# MechModule.net
KiCad netlist of a schematic drawn in EAGLE
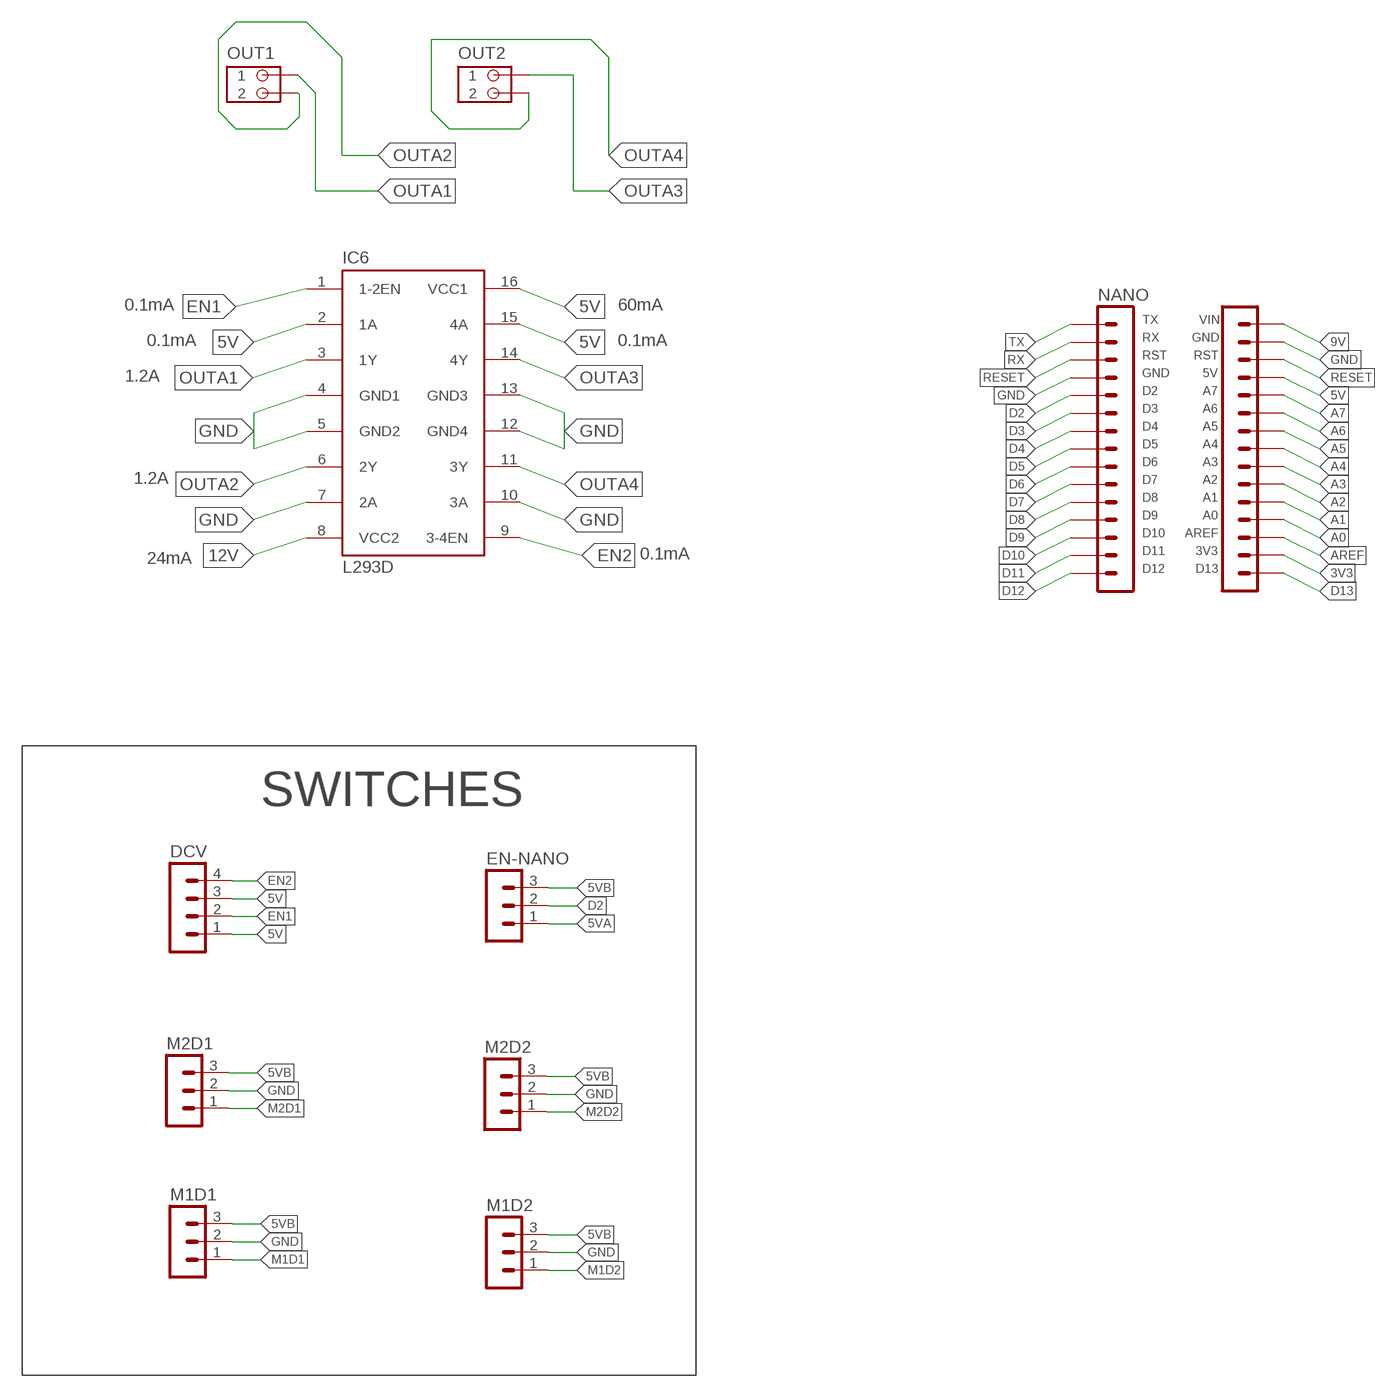
[diagram p0: schematic, sheet 1, part 1 of 3]
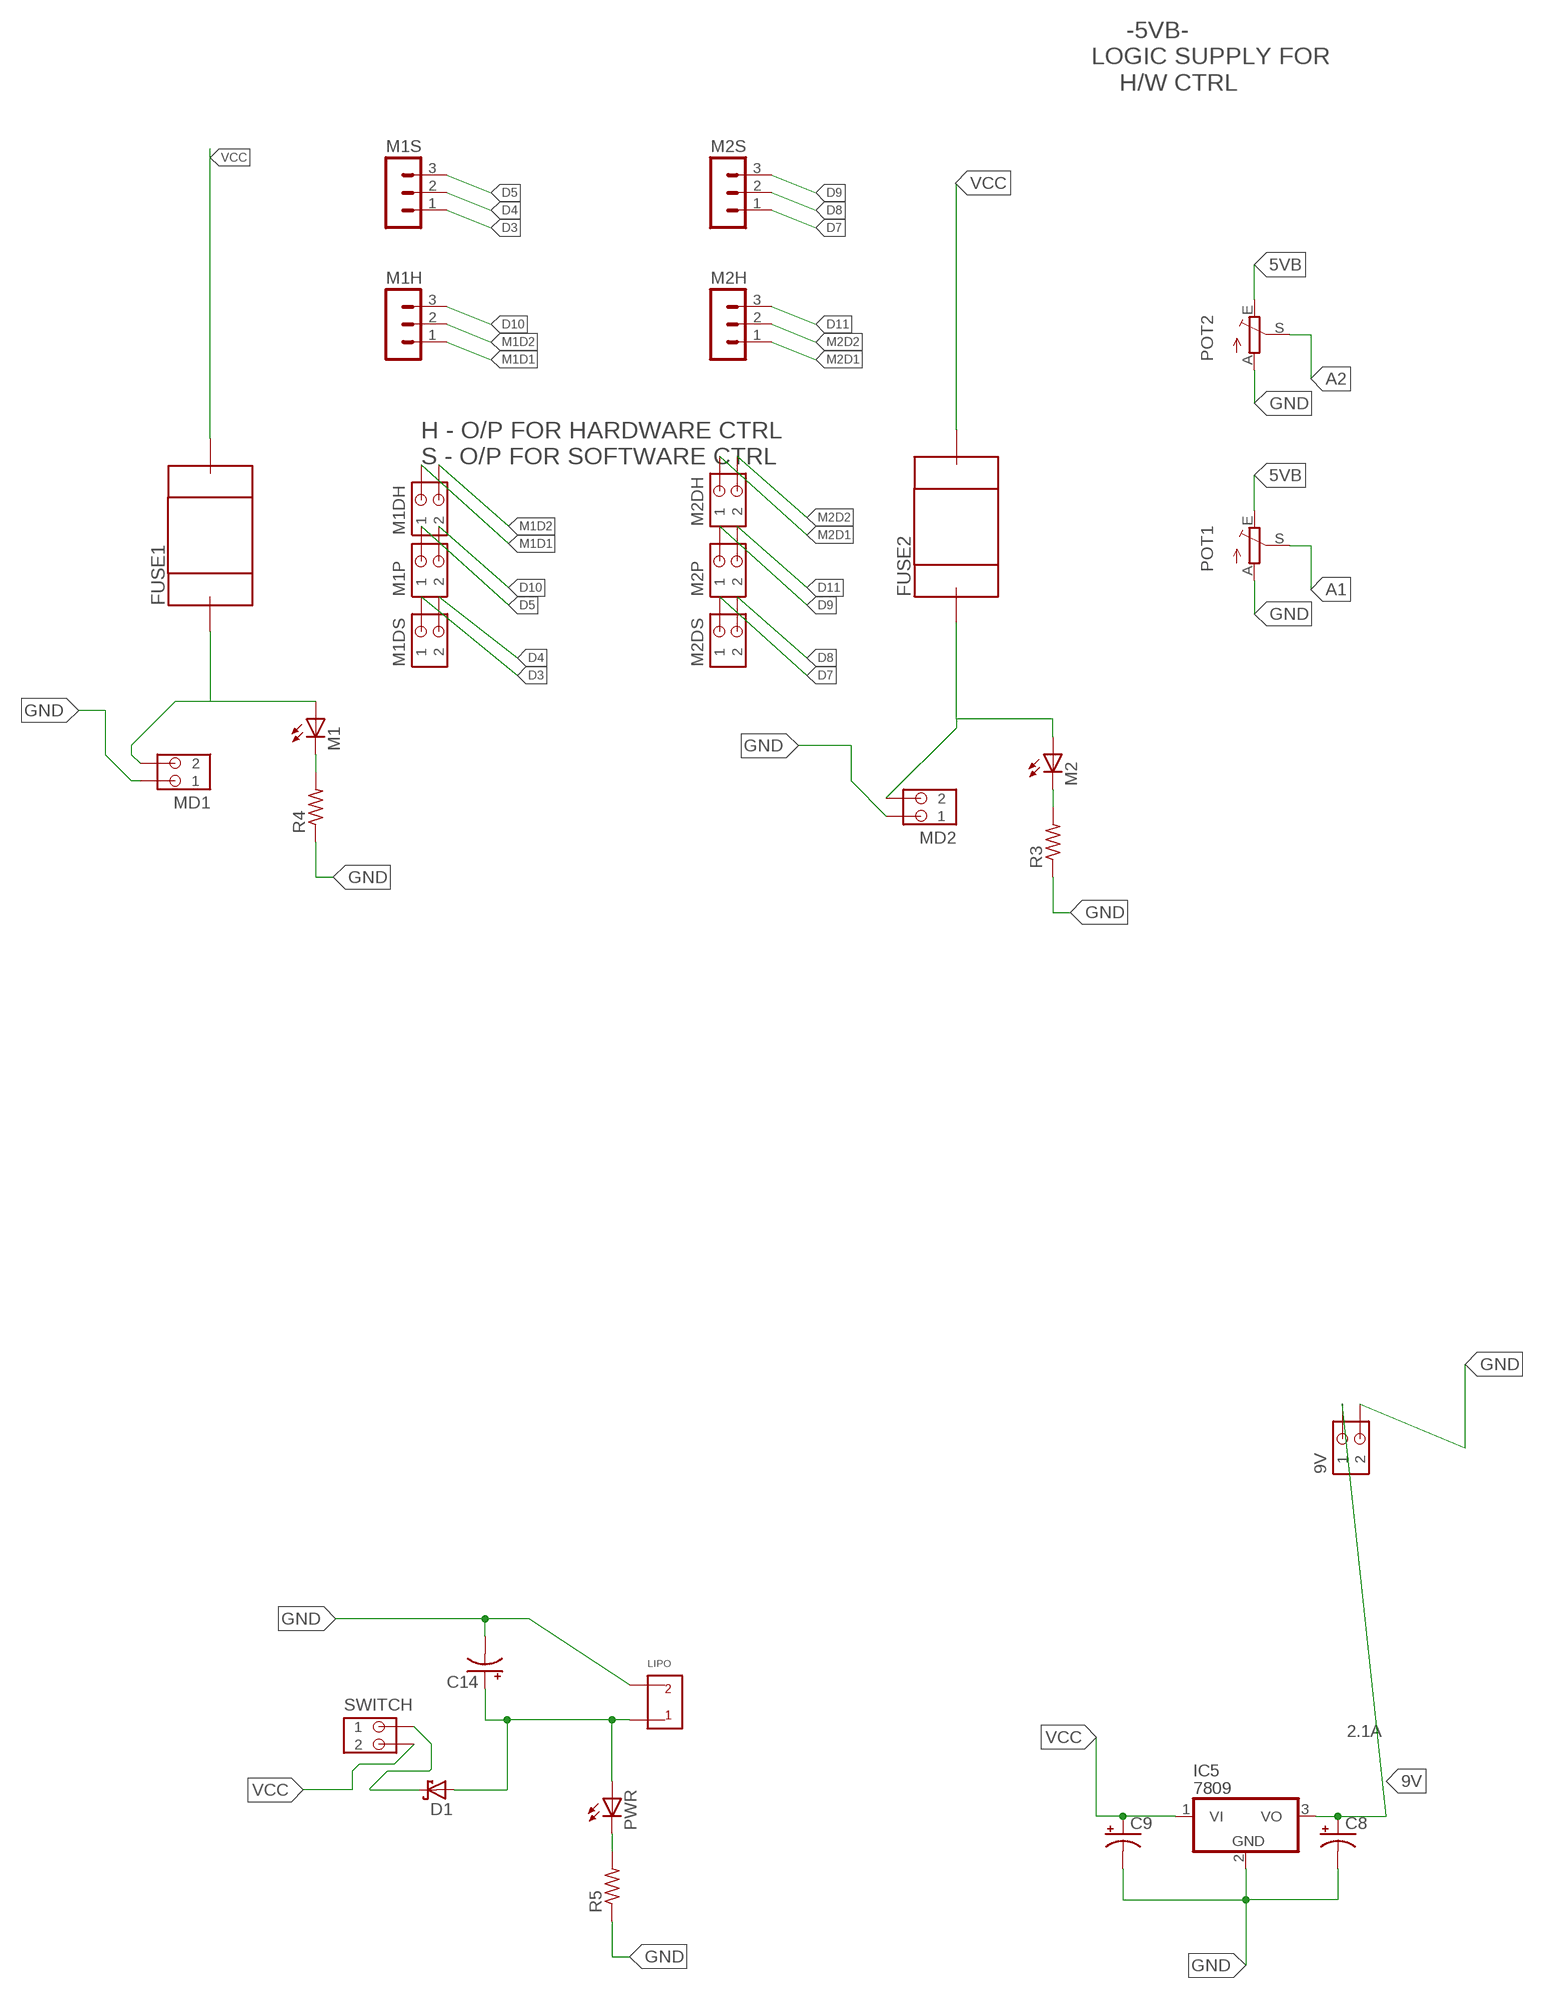
[diagram p1: schematic, sheet 1, part 2 of 3]
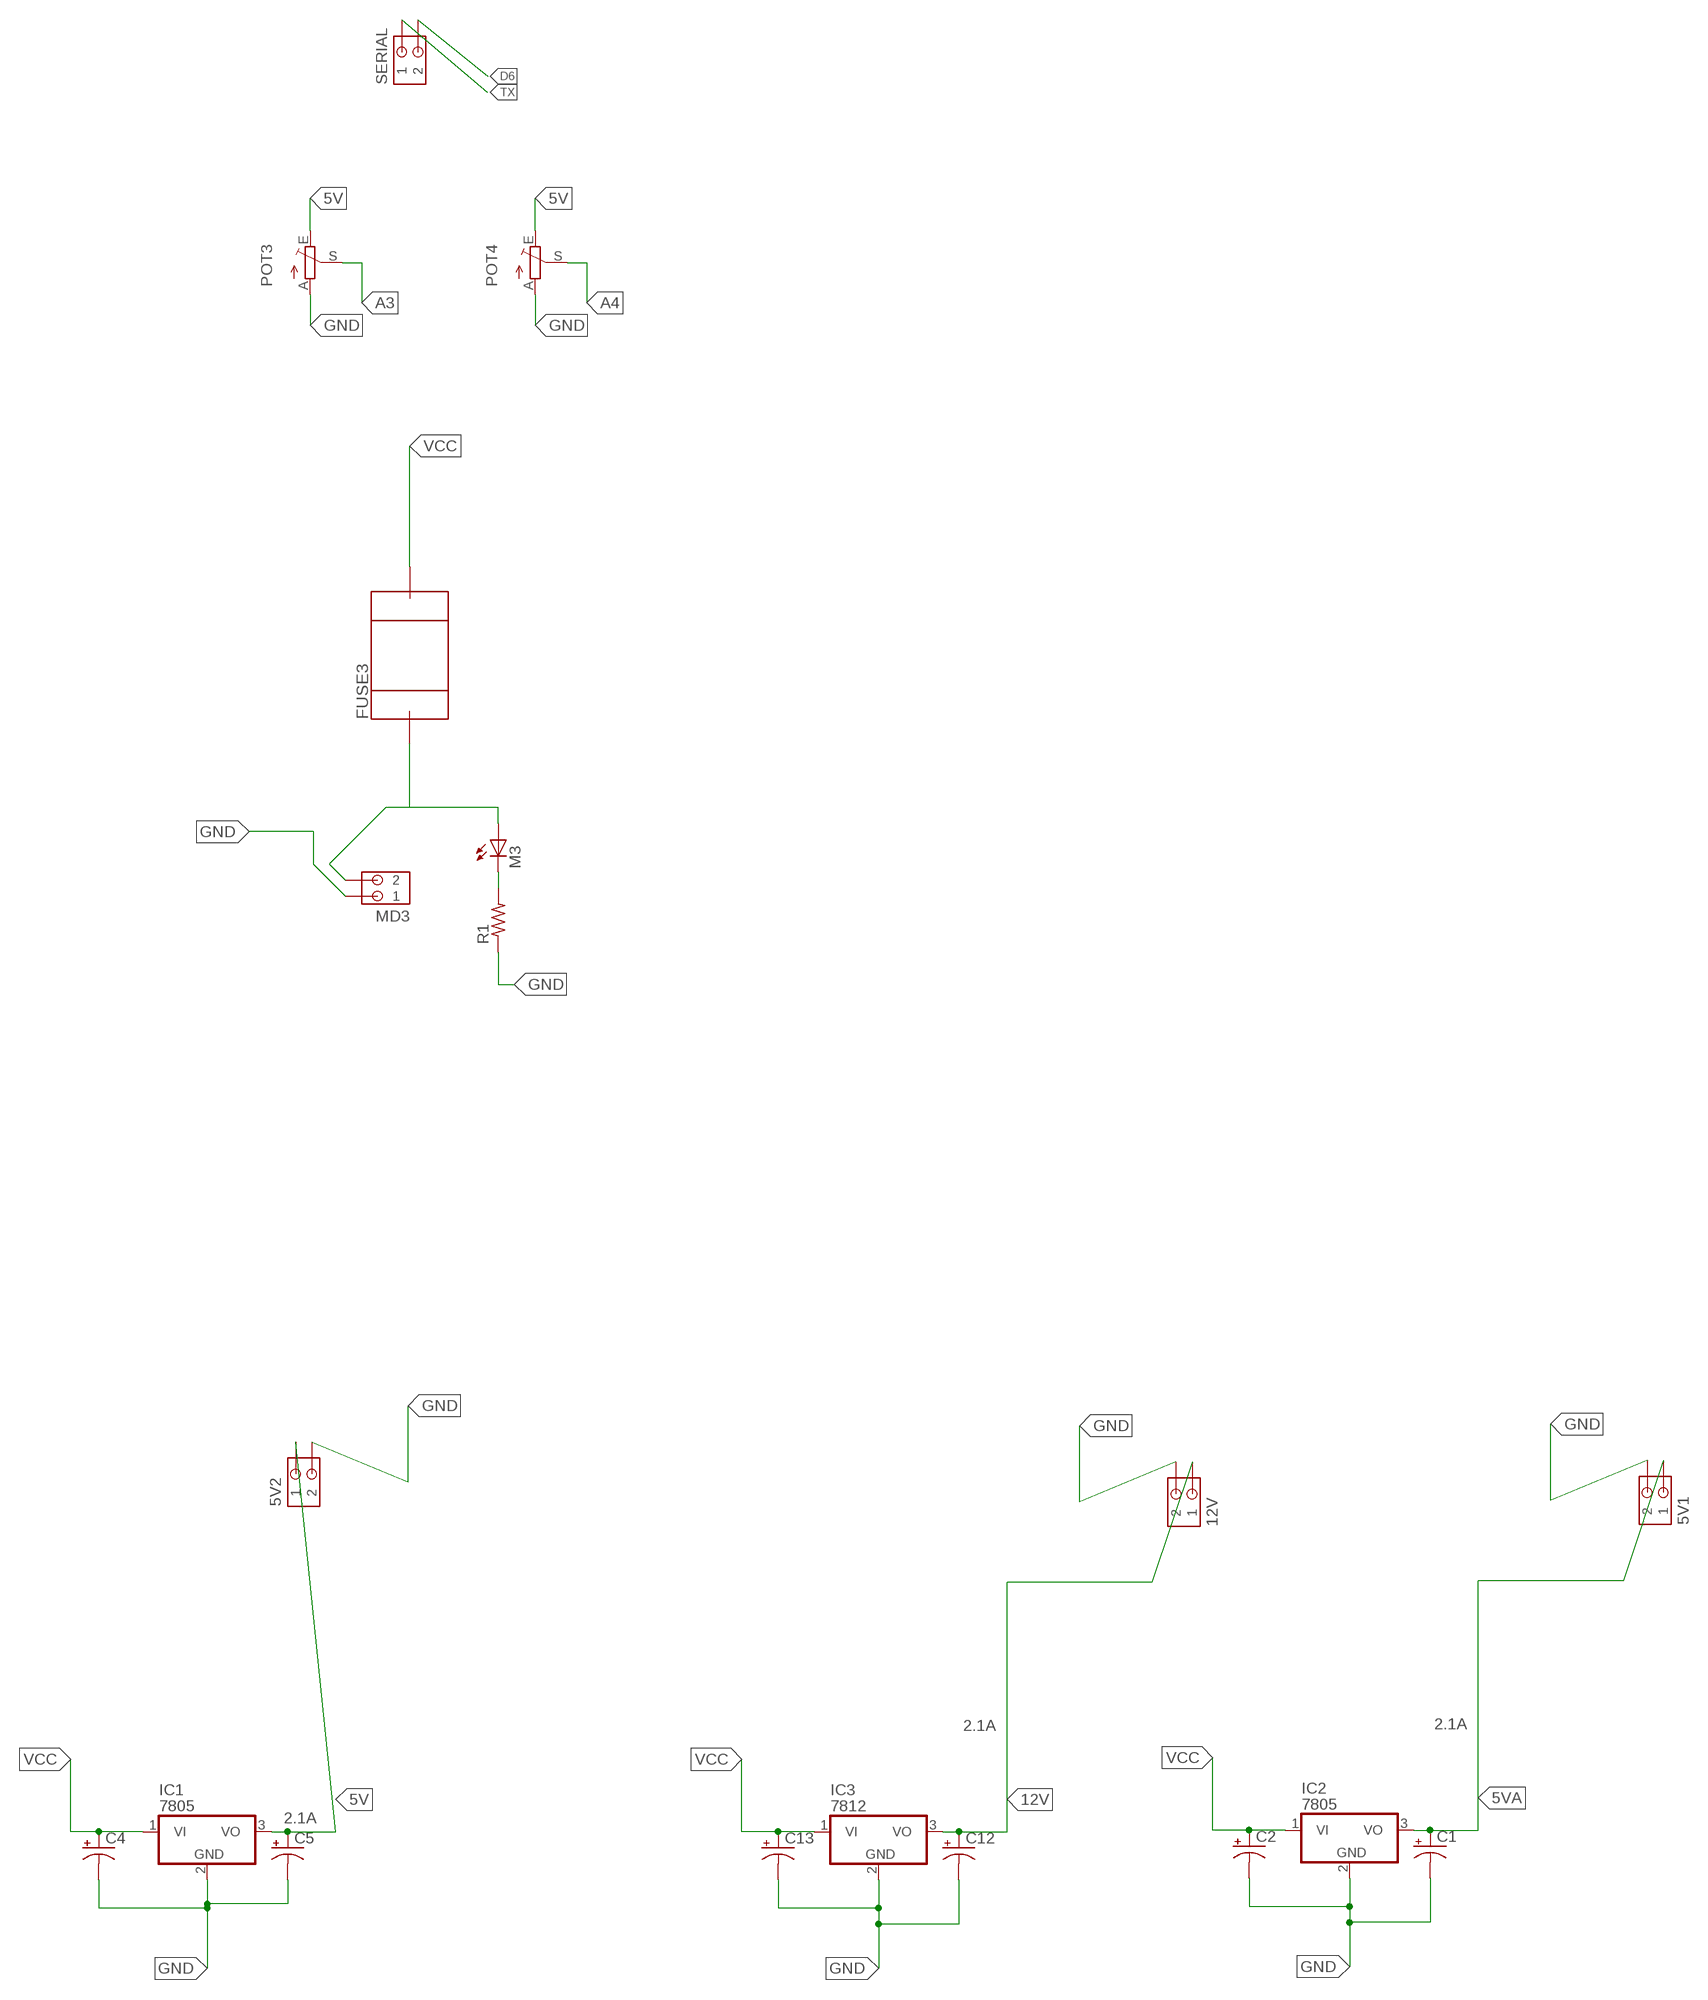
[diagram p2: schematic, sheet 1, part 3 of 3]

(export (version "E")
  (design (tool "Eeschema 10.0.6"))
  (components
    (comp (ref "5V1")
      (value "SCREWCONN")
      (footprint "eagle-import:STANDARD")
      (libsource (lib "eagle-import") (part "SCREWCONN"))
    )
    (comp (ref "5V2")
      (value "SCREWCONN")
      (footprint "eagle-import:STANDARD")
      (libsource (lib "eagle-import") (part "SCREWCONN"))
    )
    (comp (ref "9V")
      (value "SCREWCONN")
      (footprint "eagle-import:STANDARD")
      (libsource (lib "eagle-import") (part "SCREWCONN"))
    )
    (comp (ref "12V")
      (value "SCREWCONN")
      (footprint "eagle-import:STANDARD")
      (libsource (lib "eagle-import") (part "SCREWCONN"))
    )
    (comp (ref "C1")
      (value "CPOL-USE2-5")
      (footprint "eagle-import:E2-5")
      (libsource (lib "eagle-import") (part "CPOL-USE2-5"))
    )
    (comp (ref "C2")
      (value "CPOL-USE2-5")
      (footprint "eagle-import:E2-5")
      (libsource (lib "eagle-import") (part "CPOL-USE2-5"))
    )
    (comp (ref "C4")
      (value "CPOL-USE2-5")
      (footprint "eagle-import:E2-5")
      (libsource (lib "eagle-import") (part "CPOL-USE2-5"))
    )
    (comp (ref "C5")
      (value "CPOL-USE2-5")
      (footprint "eagle-import:E2-5")
      (libsource (lib "eagle-import") (part "CPOL-USE2-5"))
    )
    (comp (ref "C8")
      (value "CPOL-USE2-5")
      (footprint "eagle-import:E2-5")
      (libsource (lib "eagle-import") (part "CPOL-USE2-5"))
    )
    (comp (ref "C9")
      (value "CPOL-USE2-5")
      (footprint "eagle-import:E2-5")
      (libsource (lib "eagle-import") (part "CPOL-USE2-5"))
    )
    (comp (ref "C12")
      (value "CPOL-USE2-5")
      (footprint "eagle-import:E2-5")
      (libsource (lib "eagle-import") (part "CPOL-USE2-5"))
    )
    (comp (ref "C13")
      (value "CPOL-USE2-5")
      (footprint "eagle-import:E2-5")
      (libsource (lib "eagle-import") (part "CPOL-USE2-5"))
    )
    (comp (ref "C14")
      (value "CPOL-USE7.5-16")
      (footprint "eagle-import:E7,5-16")
      (libsource (lib "eagle-import") (part "CPOL-USE7.5-16"))
    )
    (comp (ref "D1")
      (value "5KPXX")
      (footprint "eagle-import:P6T15")
      (libsource (lib "eagle-import") (part "5KPXX"))
    )
    (comp (ref "DCV")
      (value "MA04-1")
      (footprint "eagle-import:MA04-1")
      (libsource (lib "eagle-import") (part "MA04-1"))
    )
    (comp (ref "EN-NANO")
      (value "MA03-1")
      (footprint "eagle-import:MA03-1")
      (libsource (lib "eagle-import") (part "MA03-1"))
    )
    (comp (ref "FUSE1")
      (value "CPT-FUSE")
      (footprint "eagle-import:CPT-FUSES")
      (libsource (lib "eagle-import") (part "CPT-FUSE"))
    )
    (comp (ref "FUSE2")
      (value "CPT-FUSE")
      (footprint "eagle-import:CPT-FUSES")
      (libsource (lib "eagle-import") (part "CPT-FUSE"))
    )
    (comp (ref "FUSE3")
      (value "CPT-FUSE")
      (footprint "eagle-import:CPT-FUSES")
      (libsource (lib "eagle-import") (part "CPT-FUSE"))
    )
    (comp (ref "IC1")
      (value "7805")
      (footprint "eagle-import:78XX")
      (libsource (lib "eagle-import") (part "7805"))
    )
    (comp (ref "IC2")
      (value "7805")
      (footprint "eagle-import:78XX")
      (libsource (lib "eagle-import") (part "7805"))
    )
    (comp (ref "IC3")
      (value "7812")
      (footprint "eagle-import:78XX")
      (libsource (lib "eagle-import") (part "7812"))
    )
    (comp (ref "IC5")
      (value "7809")
      (footprint "eagle-import:78XX")
      (libsource (lib "eagle-import") (part "7809"))
    )
    (comp (ref "IC6")
      (value "L293D")
      (footprint "eagle-import:DIL16")
      (libsource (lib "eagle-import") (part "L293D"))
    )
    (comp (ref "LIPO")
      (value "SCREW_XT-60")
      (footprint "eagle-import:SCREW_XT-60")
      (libsource (lib "eagle-import") (part "SCREW_XT-60"))
    )
    (comp (ref "M1")
      (value "LED5MM")
      (footprint "eagle-import:LED5MM")
      (libsource (lib "eagle-import") (part "LED5MM"))
    )
    (comp (ref "M1D1")
      (value "MA03-1")
      (footprint "eagle-import:MA03-1")
      (libsource (lib "eagle-import") (part "MA03-1"))
    )
    (comp (ref "M1D2")
      (value "MA03-1")
      (footprint "eagle-import:MA03-1")
      (libsource (lib "eagle-import") (part "MA03-1"))
    )
    (comp (ref "M1DH")
      (value "SCREWCONN")
      (footprint "eagle-import:STANDARD")
      (libsource (lib "eagle-import") (part "SCREWCONN"))
    )
    (comp (ref "M1DS")
      (value "SCREWCONN")
      (footprint "eagle-import:STANDARD")
      (libsource (lib "eagle-import") (part "SCREWCONN"))
    )
    (comp (ref "M1H")
      (value "MA03-1")
      (footprint "eagle-import:MA03-1")
      (libsource (lib "eagle-import") (part "MA03-1"))
    )
    (comp (ref "M1P")
      (value "SCREWCONN")
      (footprint "eagle-import:STANDARD")
      (libsource (lib "eagle-import") (part "SCREWCONN"))
    )
    (comp (ref "M1S")
      (value "MA03-1")
      (footprint "eagle-import:MA03-1")
      (libsource (lib "eagle-import") (part "MA03-1"))
    )
    (comp (ref "M2")
      (value "LED5MM")
      (footprint "eagle-import:LED5MM")
      (libsource (lib "eagle-import") (part "LED5MM"))
    )
    (comp (ref "M2D1")
      (value "MA03-1")
      (footprint "eagle-import:MA03-1")
      (libsource (lib "eagle-import") (part "MA03-1"))
    )
    (comp (ref "M2D2")
      (value "MA03-1")
      (footprint "eagle-import:MA03-1")
      (libsource (lib "eagle-import") (part "MA03-1"))
    )
    (comp (ref "M2DH")
      (value "SCREWCONN")
      (footprint "eagle-import:STANDARD")
      (libsource (lib "eagle-import") (part "SCREWCONN"))
    )
    (comp (ref "M2DS")
      (value "SCREWCONN")
      (footprint "eagle-import:STANDARD")
      (libsource (lib "eagle-import") (part "SCREWCONN"))
    )
    (comp (ref "M2H")
      (value "MA03-1")
      (footprint "eagle-import:MA03-1")
      (libsource (lib "eagle-import") (part "MA03-1"))
    )
    (comp (ref "M2P")
      (value "SCREWCONN")
      (footprint "eagle-import:STANDARD")
      (libsource (lib "eagle-import") (part "SCREWCONN"))
    )
    (comp (ref "M2S")
      (value "MA03-1")
      (footprint "eagle-import:MA03-1")
      (libsource (lib "eagle-import") (part "MA03-1"))
    )
    (comp (ref "M3")
      (value "LED5MM")
      (footprint "eagle-import:LED5MM")
      (libsource (lib "eagle-import") (part "LED5MM"))
    )
    (comp (ref "MD1")
      (value "SCREWCONN")
      (footprint "eagle-import:STANDARD")
      (libsource (lib "eagle-import") (part "SCREWCONN"))
    )
    (comp (ref "MD2")
      (value "SCREWCONN")
      (footprint "eagle-import:STANDARD")
      (libsource (lib "eagle-import") (part "SCREWCONN"))
    )
    (comp (ref "MD3")
      (value "SCREWCONN")
      (footprint "eagle-import:STANDARD")
      (libsource (lib "eagle-import") (part "SCREWCONN"))
    )
    (comp (ref "NANO")
      (value "ARD-NANO")
      (footprint "eagle-import:ARD-NANO")
      (libsource (lib "eagle-import") (part "ARD-NANO"))
    )
    (comp (ref "OUT1")
      (value "SCREWCONN")
      (footprint "eagle-import:STANDARD")
      (libsource (lib "eagle-import") (part "SCREWCONN"))
    )
    (comp (ref "OUT2")
      (value "SCREWCONN")
      (footprint "eagle-import:STANDARD")
      (libsource (lib "eagle-import") (part "SCREWCONN"))
    )
    (comp (ref "POT1")
      (value "TRIM_EU-CA6V")
      (footprint "eagle-import:CA6V")
      (libsource (lib "eagle-import") (part "TRIM_EU-CA6V"))
    )
    (comp (ref "POT2")
      (value "TRIM_EU-CA6V")
      (footprint "eagle-import:CA6V")
      (libsource (lib "eagle-import") (part "TRIM_EU-CA6V"))
    )
    (comp (ref "POT3")
      (value "TRIM_EU-CA6V")
      (footprint "eagle-import:CA6V")
      (libsource (lib "eagle-import") (part "TRIM_EU-CA6V"))
    )
    (comp (ref "POT4")
      (value "TRIM_EU-CA6V")
      (footprint "eagle-import:CA6V")
      (libsource (lib "eagle-import") (part "TRIM_EU-CA6V"))
    )
    (comp (ref "PWR")
      (value "LED5MM")
      (footprint "eagle-import:LED5MM")
      (libsource (lib "eagle-import") (part "LED5MM"))
    )
    (comp (ref "R1")
      (value "R-US_0204/7")
      (footprint "eagle-import:0204_7")
      (libsource (lib "eagle-import") (part "R-US_0204/7"))
    )
    (comp (ref "R3")
      (value "R-US_0204/7")
      (footprint "eagle-import:0204_7")
      (libsource (lib "eagle-import") (part "R-US_0204/7"))
    )
    (comp (ref "R4")
      (value "R-US_0204/7")
      (footprint "eagle-import:0204_7")
      (libsource (lib "eagle-import") (part "R-US_0204/7"))
    )
    (comp (ref "R5")
      (value "R-US_0204/7")
      (footprint "eagle-import:0204_7")
      (libsource (lib "eagle-import") (part "R-US_0204/7"))
    )
    (comp (ref "SERIAL")
      (value "SCREWCONN")
      (footprint "eagle-import:STANDARD")
      (libsource (lib "eagle-import") (part "SCREWCONN"))
    )
    (comp (ref "SWITCH")
      (value "SCREWCONN")
      (footprint "eagle-import:STANDARD")
      (libsource (lib "eagle-import") (part "SCREWCONN"))
    )
  )
  (nets
    (net (code "1") (name "3V3") (class "Default")
      (node (ref "NANO") (pin "3V3") (pinfunction "3V3_3V3") (pintype "passive"))
    )
    (net (code "2") (name "5V") (class "Default")
      (node (ref "5V2") (pin "3") (pinfunction "1_3") (pintype "bidirectional"))
      (node (ref "C5") (pin "+") (pinfunction "+_+") (pintype "passive"))
      (node (ref "DCV") (pin "1") (pinfunction "1_1") (pintype "passive"))
      (node (ref "DCV") (pin "3") (pinfunction "3_3") (pintype "passive"))
      (node (ref "IC1") (pin "3") (pinfunction "VO_3") (pintype "passive"))
      (node (ref "IC6") (pin "15") (pinfunction "4A_15") (pintype "input"))
      (node (ref "IC6") (pin "16") (pinfunction "VCC1_16") (pintype "power_in"))
      (node (ref "IC6") (pin "2") (pinfunction "1A_2") (pintype "input"))
      (node (ref "NANO") (pin "5V") (pinfunction "5V_5V") (pintype "passive"))
      (node (ref "POT3") (pin "E") (pinfunction "E_E") (pintype "passive"))
      (node (ref "POT4") (pin "E") (pinfunction "E_E") (pintype "passive"))
    )
    (net (code "3") (name "5VA") (class "Default")
      (node (ref "5V1") (pin "3") (pinfunction "1_3") (pintype "bidirectional"))
      (node (ref "C1") (pin "+") (pinfunction "+_+") (pintype "passive"))
      (node (ref "EN-NANO") (pin "1") (pinfunction "1_1") (pintype "passive"))
      (node (ref "IC2") (pin "3") (pinfunction "VO_3") (pintype "passive"))
    )
    (net (code "4") (name "5VB") (class "Default")
      (node (ref "EN-NANO") (pin "3") (pinfunction "3_3") (pintype "passive"))
      (node (ref "M1D1") (pin "3") (pinfunction "3_3") (pintype "passive"))
      (node (ref "M1D2") (pin "3") (pinfunction "3_3") (pintype "passive"))
      (node (ref "M2D1") (pin "3") (pinfunction "3_3") (pintype "passive"))
      (node (ref "M2D2") (pin "3") (pinfunction "3_3") (pintype "passive"))
      (node (ref "POT1") (pin "E") (pinfunction "E_E") (pintype "passive"))
      (node (ref "POT2") (pin "E") (pinfunction "E_E") (pintype "passive"))
    )
    (net (code "5") (name "9V") (class "Default")
      (node (ref "9V") (pin "3") (pinfunction "1_3") (pintype "bidirectional"))
      (node (ref "C8") (pin "+") (pinfunction "+_+") (pintype "passive"))
      (node (ref "IC5") (pin "3") (pinfunction "VO_3") (pintype "passive"))
      (node (ref "NANO") (pin "VIN") (pinfunction "VIN_VIN") (pintype "passive"))
    )
    (net (code "6") (name "12V") (class "Default")
      (node (ref "12V") (pin "3") (pinfunction "1_3") (pintype "bidirectional"))
      (node (ref "C12") (pin "+") (pinfunction "+_+") (pintype "passive"))
      (node (ref "IC3") (pin "3") (pinfunction "VO_3") (pintype "passive"))
      (node (ref "IC6") (pin "8") (pinfunction "VCC2_8") (pintype "power_in"))
    )
    (net (code "7") (name "A0") (class "Default")
      (node (ref "NANO") (pin "A0") (pinfunction "A0_A0") (pintype "passive"))
    )
    (net (code "8") (name "A1") (class "Default")
      (node (ref "NANO") (pin "A1") (pinfunction "A1_A1") (pintype "passive"))
      (node (ref "POT1") (pin "S") (pinfunction "S_S") (pintype "passive"))
    )
    (net (code "9") (name "A2") (class "Default")
      (node (ref "NANO") (pin "A2") (pinfunction "A2_A2") (pintype "passive"))
      (node (ref "POT2") (pin "S") (pinfunction "S_S") (pintype "passive"))
    )
    (net (code "10") (name "A3") (class "Default")
      (node (ref "NANO") (pin "A3") (pinfunction "A3_A3") (pintype "passive"))
      (node (ref "POT3") (pin "S") (pinfunction "S_S") (pintype "passive"))
    )
    (net (code "11") (name "A4") (class "Default")
      (node (ref "NANO") (pin "A4") (pinfunction "A4_A4") (pintype "passive"))
      (node (ref "POT4") (pin "S") (pinfunction "S_S") (pintype "passive"))
    )
    (net (code "12") (name "A5") (class "Default")
      (node (ref "NANO") (pin "A5") (pinfunction "A5_A5") (pintype "passive"))
    )
    (net (code "13") (name "A6") (class "Default")
      (node (ref "NANO") (pin "A6") (pinfunction "A6_A6") (pintype "passive"))
    )
    (net (code "14") (name "A7") (class "Default")
      (node (ref "NANO") (pin "A7") (pinfunction "A7_A7") (pintype "passive"))
    )
    (net (code "15") (name "AREF") (class "Default")
      (node (ref "NANO") (pin "AREF") (pinfunction "AREF_AREF") (pintype "passive"))
    )
    (net (code "16") (name "D2") (class "Default")
      (node (ref "EN-NANO") (pin "2") (pinfunction "2_2") (pintype "passive"))
      (node (ref "NANO") (pin "D2") (pinfunction "D2_D2") (pintype "passive"))
    )
    (net (code "17") (name "D3") (class "Default")
      (node (ref "M1DS") (pin "3") (pinfunction "1_3") (pintype "bidirectional"))
      (node (ref "M1S") (pin "1") (pinfunction "1_1") (pintype "passive"))
      (node (ref "NANO") (pin "D3") (pinfunction "D3_D3") (pintype "passive"))
    )
    (net (code "18") (name "D4") (class "Default")
      (node (ref "M1DS") (pin "4") (pinfunction "2_4") (pintype "bidirectional"))
      (node (ref "M1S") (pin "2") (pinfunction "2_2") (pintype "passive"))
      (node (ref "NANO") (pin "D4") (pinfunction "D4_D4") (pintype "passive"))
    )
    (net (code "19") (name "D5") (class "Default")
      (node (ref "M1P") (pin "3") (pinfunction "1_3") (pintype "bidirectional"))
      (node (ref "M1S") (pin "3") (pinfunction "3_3") (pintype "passive"))
      (node (ref "NANO") (pin "D5") (pinfunction "D5_D5") (pintype "passive"))
    )
    (net (code "20") (name "D6") (class "Default")
      (node (ref "NANO") (pin "D6") (pinfunction "D6_D6") (pintype "passive"))
      (node (ref "SERIAL") (pin "4") (pinfunction "2_4") (pintype "bidirectional"))
    )
    (net (code "21") (name "D7") (class "Default")
      (node (ref "M2DS") (pin "3") (pinfunction "1_3") (pintype "bidirectional"))
      (node (ref "M2S") (pin "1") (pinfunction "1_1") (pintype "passive"))
      (node (ref "NANO") (pin "D7") (pinfunction "D7_D7") (pintype "passive"))
    )
    (net (code "22") (name "D8") (class "Default")
      (node (ref "M2DS") (pin "4") (pinfunction "2_4") (pintype "bidirectional"))
      (node (ref "M2S") (pin "2") (pinfunction "2_2") (pintype "passive"))
      (node (ref "NANO") (pin "D8") (pinfunction "D8_D8") (pintype "passive"))
    )
    (net (code "23") (name "D9") (class "Default")
      (node (ref "M2P") (pin "3") (pinfunction "1_3") (pintype "bidirectional"))
      (node (ref "M2S") (pin "3") (pinfunction "3_3") (pintype "passive"))
      (node (ref "NANO") (pin "D9") (pinfunction "D9_D9") (pintype "passive"))
    )
    (net (code "24") (name "D10") (class "Default")
      (node (ref "M1H") (pin "3") (pinfunction "3_3") (pintype "passive"))
      (node (ref "M1P") (pin "4") (pinfunction "2_4") (pintype "bidirectional"))
      (node (ref "NANO") (pin "D10") (pinfunction "D10_D10") (pintype "passive"))
    )
    (net (code "25") (name "D11") (class "Default")
      (node (ref "M2H") (pin "3") (pinfunction "3_3") (pintype "passive"))
      (node (ref "M2P") (pin "4") (pinfunction "2_4") (pintype "bidirectional"))
      (node (ref "NANO") (pin "D11") (pinfunction "D11_D11") (pintype "passive"))
    )
    (net (code "26") (name "D12") (class "Default")
      (node (ref "NANO") (pin "D12") (pinfunction "D12_D12") (pintype "passive"))
    )
    (net (code "27") (name "D13") (class "Default")
      (node (ref "NANO") (pin "D13") (pinfunction "D13_D13") (pintype "passive"))
    )
    (net (code "28") (name "EN1") (class "Default")
      (node (ref "DCV") (pin "2") (pinfunction "2_2") (pintype "passive"))
      (node (ref "IC6") (pin "1") (pinfunction "1-2EN_1") (pintype "input"))
    )
    (net (code "29") (name "EN2") (class "Default")
      (node (ref "DCV") (pin "4") (pinfunction "4_4") (pintype "passive"))
      (node (ref "IC6") (pin "9") (pinfunction "3-4EN_9") (pintype "input"))
    )
    (net (code "30") (name "GND") (class "Default")
      (node (ref "12V") (pin "4") (pinfunction "2_4") (pintype "bidirectional"))
      (node (ref "5V1") (pin "4") (pinfunction "2_4") (pintype "bidirectional"))
      (node (ref "5V2") (pin "4") (pinfunction "2_4") (pintype "bidirectional"))
      (node (ref "9V") (pin "4") (pinfunction "2_4") (pintype "bidirectional"))
      (node (ref "C1") (pin "-") (pinfunction "-_-") (pintype "passive"))
      (node (ref "C12") (pin "-") (pinfunction "-_-") (pintype "passive"))
      (node (ref "C13") (pin "-") (pinfunction "-_-") (pintype "passive"))
      (node (ref "C14") (pin "-") (pinfunction "-_-") (pintype "passive"))
      (node (ref "C2") (pin "-") (pinfunction "-_-") (pintype "passive"))
      (node (ref "C4") (pin "-") (pinfunction "-_-") (pintype "passive"))
      (node (ref "C5") (pin "-") (pinfunction "-_-") (pintype "passive"))
      (node (ref "C8") (pin "-") (pinfunction "-_-") (pintype "passive"))
      (node (ref "C9") (pin "-") (pinfunction "-_-") (pintype "passive"))
      (node (ref "IC1") (pin "2") (pinfunction "GND_2") (pintype "passive"))
      (node (ref "IC2") (pin "2") (pinfunction "GND_2") (pintype "passive"))
      (node (ref "IC3") (pin "2") (pinfunction "GND_2") (pintype "passive"))
      (node (ref "IC5") (pin "2") (pinfunction "GND_2") (pintype "passive"))
      (node (ref "IC6") (pin "10") (pinfunction "3A_10") (pintype "input"))
      (node (ref "IC6") (pin "12") (pinfunction "GND4_12") (pintype "power_in"))
      (node (ref "IC6") (pin "13") (pinfunction "GND3_13") (pintype "power_in"))
      (node (ref "IC6") (pin "4") (pinfunction "GND1_4") (pintype "power_in"))
      (node (ref "IC6") (pin "5") (pinfunction "GND2_5") (pintype "power_in"))
      (node (ref "IC6") (pin "7") (pinfunction "2A_7") (pintype "input"))
      (node (ref "LIPO") (pin "P$2") (pinfunction "P$2_P$2") (pintype "bidirectional"))
      (node (ref "M1D1") (pin "2") (pinfunction "2_2") (pintype "passive"))
      (node (ref "M1D2") (pin "2") (pinfunction "2_2") (pintype "passive"))
      (node (ref "M2D1") (pin "2") (pinfunction "2_2") (pintype "passive"))
      (node (ref "M2D2") (pin "2") (pinfunction "2_2") (pintype "passive"))
      (node (ref "MD1") (pin "3") (pinfunction "1_3") (pintype "bidirectional"))
      (node (ref "MD2") (pin "3") (pinfunction "1_3") (pintype "bidirectional"))
      (node (ref "MD3") (pin "3") (pinfunction "1_3") (pintype "bidirectional"))
      (node (ref "NANO") (pin "GND1") (pinfunction "GND1_GND1") (pintype "passive"))
      (node (ref "NANO") (pin "GND2") (pinfunction "GND2_GND2") (pintype "passive"))
      (node (ref "POT1") (pin "A") (pinfunction "A_A") (pintype "passive"))
      (node (ref "POT2") (pin "A") (pinfunction "A_A") (pintype "passive"))
      (node (ref "POT3") (pin "A") (pinfunction "A_A") (pintype "passive"))
      (node (ref "POT4") (pin "A") (pinfunction "A_A") (pintype "passive"))
      (node (ref "R1") (pin "1") (pinfunction "1_1") (pintype "passive"))
      (node (ref "R3") (pin "1") (pinfunction "1_1") (pintype "passive"))
      (node (ref "R4") (pin "1") (pinfunction "1_1") (pintype "passive"))
      (node (ref "R5") (pin "1") (pinfunction "1_1") (pintype "passive"))
    )
    (net (code "31") (name "M1D1") (class "Default")
      (node (ref "M1D1") (pin "1") (pinfunction "1_1") (pintype "passive"))
      (node (ref "M1DH") (pin "3") (pinfunction "1_3") (pintype "bidirectional"))
      (node (ref "M1H") (pin "1") (pinfunction "1_1") (pintype "passive"))
    )
    (net (code "32") (name "M1D2") (class "Default")
      (node (ref "M1D2") (pin "1") (pinfunction "1_1") (pintype "passive"))
      (node (ref "M1DH") (pin "4") (pinfunction "2_4") (pintype "bidirectional"))
      (node (ref "M1H") (pin "2") (pinfunction "2_2") (pintype "passive"))
    )
    (net (code "33") (name "M2D1") (class "Default")
      (node (ref "M2D1") (pin "1") (pinfunction "1_1") (pintype "passive"))
      (node (ref "M2DH") (pin "3") (pinfunction "1_3") (pintype "bidirectional"))
      (node (ref "M2H") (pin "1") (pinfunction "1_1") (pintype "passive"))
    )
    (net (code "34") (name "M2D2") (class "Default")
      (node (ref "M2D2") (pin "1") (pinfunction "1_1") (pintype "passive"))
      (node (ref "M2DH") (pin "4") (pinfunction "2_4") (pintype "bidirectional"))
      (node (ref "M2H") (pin "2") (pinfunction "2_2") (pintype "passive"))
    )
    (net (code "35") (name "Net-(C14-Pad+)") (class "Default")
      (node (ref "C14") (pin "+") (pinfunction "+_+") (pintype "passive"))
      (node (ref "D1") (pin "A") (pinfunction "A_A") (pintype "passive"))
      (node (ref "LIPO") (pin "P$1") (pinfunction "P$1_P$1") (pintype "bidirectional"))
      (node (ref "PWR") (pin "A") (pinfunction "A_A") (pintype "passive"))
    )
    (net (code "36") (name "Net-(M1-C)") (class "Default")
      (node (ref "M1") (pin "K") (pinfunction "C_K") (pintype "passive"))
      (node (ref "R4") (pin "2") (pinfunction "2_2") (pintype "passive"))
    )
    (net (code "37") (name "Net-(M2-C)") (class "Default")
      (node (ref "M2") (pin "K") (pinfunction "C_K") (pintype "passive"))
      (node (ref "R3") (pin "2") (pinfunction "2_2") (pintype "passive"))
    )
    (net (code "38") (name "Net-(M3-C)") (class "Default")
      (node (ref "M3") (pin "K") (pinfunction "C_K") (pintype "passive"))
      (node (ref "R1") (pin "2") (pinfunction "2_2") (pintype "passive"))
    )
    (net (code "39") (name "Net-(MD1-2)") (class "Default")
      (node (ref "FUSE1") (pin "P$1") (pinfunction "P$1_P$1") (pintype "bidirectional"))
      (node (ref "M1") (pin "A") (pinfunction "A_A") (pintype "passive"))
      (node (ref "MD1") (pin "4") (pinfunction "2_4") (pintype "bidirectional"))
    )
    (net (code "40") (name "Net-(MD2-2)") (class "Default")
      (node (ref "FUSE2") (pin "P$1") (pinfunction "P$1_P$1") (pintype "bidirectional"))
      (node (ref "M2") (pin "A") (pinfunction "A_A") (pintype "passive"))
      (node (ref "MD2") (pin "4") (pinfunction "2_4") (pintype "bidirectional"))
    )
    (net (code "41") (name "Net-(MD3-2)") (class "Default")
      (node (ref "FUSE3") (pin "P$1") (pinfunction "P$1_P$1") (pintype "bidirectional"))
      (node (ref "M3") (pin "A") (pinfunction "A_A") (pintype "passive"))
      (node (ref "MD3") (pin "4") (pinfunction "2_4") (pintype "bidirectional"))
    )
    (net (code "42") (name "Net-(PWR-C)") (class "Default")
      (node (ref "PWR") (pin "K") (pinfunction "C_K") (pintype "passive"))
      (node (ref "R5") (pin "2") (pinfunction "2_2") (pintype "passive"))
    )
    (net (code "43") (name "Net-(SWITCH-1)") (class "Default")
      (node (ref "D1") (pin "C") (pinfunction "C_C") (pintype "passive"))
      (node (ref "SWITCH") (pin "3") (pinfunction "1_3") (pintype "bidirectional"))
    )
    (net (code "44") (name "OUTA1") (class "Default")
      (node (ref "IC6") (pin "3") (pinfunction "1Y_3") (pintype "output"))
      (node (ref "OUT1") (pin "3") (pinfunction "1_3") (pintype "bidirectional"))
    )
    (net (code "45") (name "OUTA2") (class "Default")
      (node (ref "IC6") (pin "6") (pinfunction "2Y_6") (pintype "output"))
      (node (ref "OUT1") (pin "4") (pinfunction "2_4") (pintype "bidirectional"))
    )
    (net (code "46") (name "OUTA3") (class "Default")
      (node (ref "IC6") (pin "14") (pinfunction "4Y_14") (pintype "output"))
      (node (ref "OUT2") (pin "3") (pinfunction "1_3") (pintype "bidirectional"))
    )
    (net (code "47") (name "OUTA4") (class "Default")
      (node (ref "IC6") (pin "11") (pinfunction "3Y_11") (pintype "output"))
      (node (ref "OUT2") (pin "4") (pinfunction "2_4") (pintype "bidirectional"))
    )
    (net (code "48") (name "RESET") (class "Default")
      (node (ref "NANO") (pin "RST1") (pinfunction "RST1_RST1") (pintype "passive"))
      (node (ref "NANO") (pin "RST2") (pinfunction "RST2_RST2") (pintype "passive"))
    )
    (net (code "49") (name "RX") (class "Default")
      (node (ref "NANO") (pin "RX") (pinfunction "RX_RX") (pintype "passive"))
    )
    (net (code "50") (name "TX") (class "Default")
      (node (ref "NANO") (pin "TX") (pinfunction "TX_TX") (pintype "passive"))
      (node (ref "SERIAL") (pin "3") (pinfunction "1_3") (pintype "bidirectional"))
    )
    (net (code "51") (name "VCC") (class "Default")
      (node (ref "C13") (pin "+") (pinfunction "+_+") (pintype "passive"))
      (node (ref "C2") (pin "+") (pinfunction "+_+") (pintype "passive"))
      (node (ref "C4") (pin "+") (pinfunction "+_+") (pintype "passive"))
      (node (ref "C9") (pin "+") (pinfunction "+_+") (pintype "passive"))
      (node (ref "FUSE1") (pin "P$2") (pinfunction "P$2_P$2") (pintype "bidirectional"))
      (node (ref "FUSE2") (pin "P$2") (pinfunction "P$2_P$2") (pintype "bidirectional"))
      (node (ref "FUSE3") (pin "P$2") (pinfunction "P$2_P$2") (pintype "bidirectional"))
      (node (ref "IC1") (pin "1") (pinfunction "VI_1") (pintype "input"))
      (node (ref "IC2") (pin "1") (pinfunction "VI_1") (pintype "input"))
      (node (ref "IC3") (pin "1") (pinfunction "VI_1") (pintype "input"))
      (node (ref "IC5") (pin "1") (pinfunction "VI_1") (pintype "input"))
      (node (ref "SWITCH") (pin "4") (pinfunction "2_4") (pintype "bidirectional"))
    )
  )
)
